# picoAvaR5.net
KiCad netlist of a schematic drawn in EAGLE
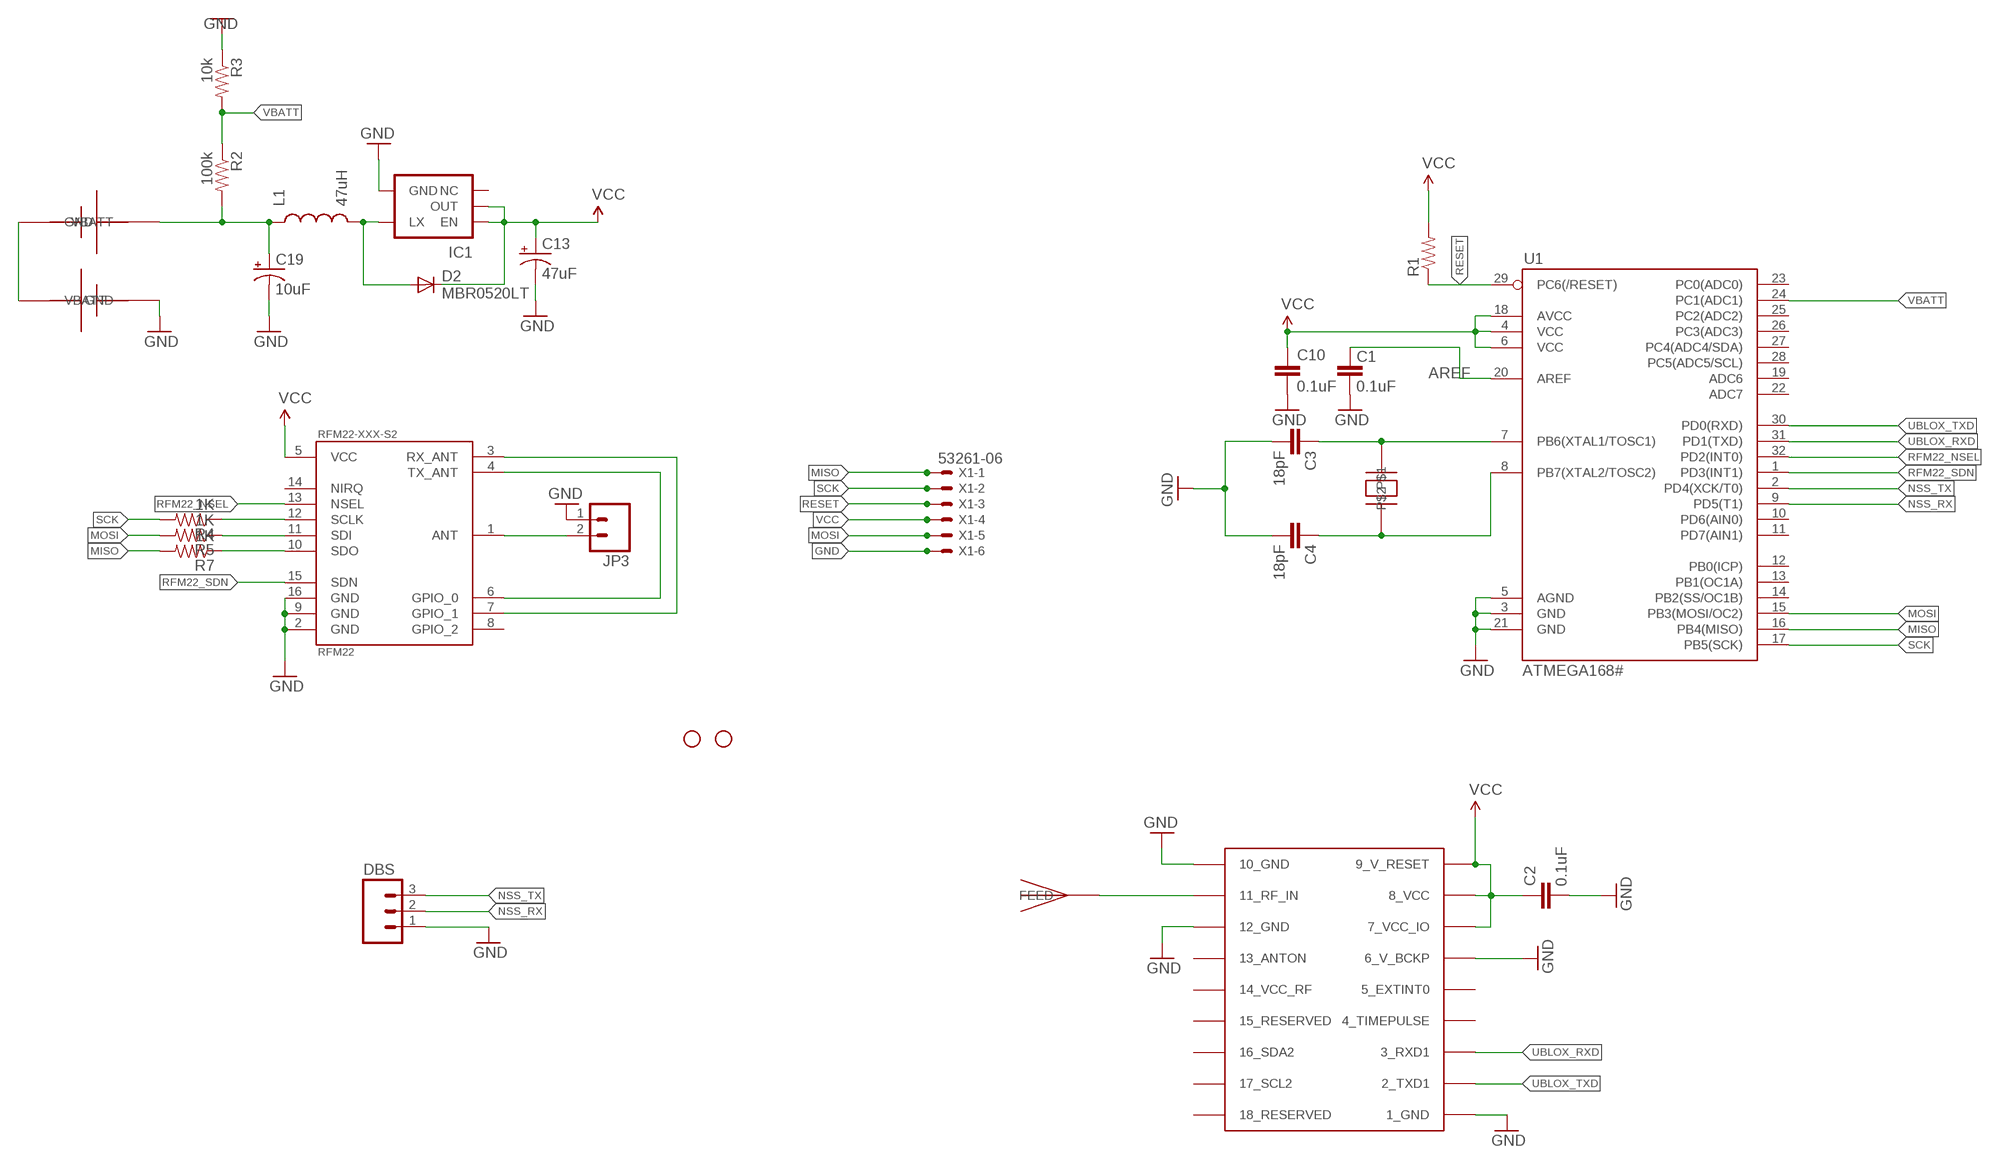
[diagram p0: schematic, sheet 1]

(export (version "E")
  (design (tool "Eeschema 10.0.6"))
  (components
    (comp (ref "C1")
      (value "0.1uF")
      (footprint "eagle-import:0402-CAP")
      (libsource (lib "eagle-import") (part "CAP0402-CAP"))
    )
    (comp (ref "C2")
      (value "0.1uF")
      (footprint "eagle-import:0402-CAP")
      (libsource (lib "eagle-import") (part "CAP0402-CAP"))
    )
    (comp (ref "C3")
      (value "18pF")
      (footprint "eagle-import:0402-CAP")
      (libsource (lib "eagle-import") (part "CAP0402-CAP"))
    )
    (comp (ref "C4")
      (value "18pF")
      (footprint "eagle-import:0402-CAP")
      (libsource (lib "eagle-import") (part "CAP0402-CAP"))
    )
    (comp (ref "C10")
      (value "0.1uF")
      (footprint "eagle-import:0402-CAP")
      (libsource (lib "eagle-import") (part "CAP0402-CAP"))
    )
    (comp (ref "C13")
      (value "47uF")
      (footprint "eagle-import:EIA3216")
      (libsource (lib "eagle-import") (part "CAP_POL1206"))
    )
    (comp (ref "C19")
      (value "10uF")
      (footprint "eagle-import:EIA3216")
      (libsource (lib "eagle-import") (part "CAP_POL1206"))
    )
    (comp (ref "D2")
      (value "MBR0520LT")
      (footprint "eagle-import:SOD123")
      (libsource (lib "eagle-import") (part "MBR0520LT"))
    )
    (comp (ref "DBS")
      (value "M03PTH")
      (footprint "eagle-import:1X03")
      (libsource (lib "eagle-import") (part "M03PTH"))
    )
    (comp (ref "IC1")
      (value "V_REG_NCP1400SOT23-5")
      (footprint "eagle-import:SOT23-5")
      (libsource (lib "eagle-import") (part "V_REG_NCP1400SOT23-5"))
    )
    (comp (ref "JP1")
      (value "STAND-OFF")
      (footprint "eagle-import:STAND-OFF")
      (libsource (lib "eagle-import") (part "STAND-OFF"))
    )
    (comp (ref "JP2")
      (value "STAND-OFF")
      (footprint "eagle-import:STAND-OFF")
      (libsource (lib "eagle-import") (part "STAND-OFF"))
    )
    (comp (ref "JP3")
      (value "M02PTH")
      (footprint "eagle-import:1X02")
      (libsource (lib "eagle-import") (part "M02PTH"))
    )
    (comp (ref "L1")
      (value "47uH")
      (footprint "eagle-import:1210")
      (libsource (lib "eagle-import") (part "INDUCTOR1210"))
    )
    (comp (ref "R1")
      (value "RESISTOR0402-RES")
      (footprint "eagle-import:0402-RES")
      (libsource (lib "eagle-import") (part "RESISTOR0402-RES"))
    )
    (comp (ref "R2")
      (value "100k")
      (footprint "eagle-import:0402-RES")
      (libsource (lib "eagle-import") (part "RESISTOR0402-RES"))
    )
    (comp (ref "R3")
      (value "10k")
      (footprint "eagle-import:0402-RES")
      (libsource (lib "eagle-import") (part "RESISTOR0402-RES"))
    )
    (comp (ref "R4")
      (value "1K")
      (footprint "eagle-import:0402-RES")
      (libsource (lib "eagle-import") (part "RESISTOR0402-RES"))
    )
    (comp (ref "R5")
      (value "1K")
      (footprint "eagle-import:0402-RES")
      (libsource (lib "eagle-import") (part "RESISTOR0402-RES"))
    )
    (comp (ref "R7")
      (value "1K")
      (footprint "eagle-import:0402-RES")
      (libsource (lib "eagle-import") (part "RESISTOR0402-RES"))
    )
    (comp (ref "RFM22-XXX-S2")
      (value "RFM22")
      (footprint "eagle-import:RFM22-XXX-S2")
      (libsource (lib "eagle-import") (part "RFM22"))
    )
    (comp (ref "U$1")
      (value "UBLOX_MAX-6")
      (footprint "eagle-import:UBLOX_MAX-6")
      (libsource (lib "eagle-import") (part "UBLOX_MAX-6"))
    )
    (comp (ref "U$2")
      (value "ABRACON_ABM3_CRYSTAL")
      (footprint "eagle-import:ABRACON_ABM3_CRYSTAL")
      (libsource (lib "eagle-import") (part "ABRACON_ABM3_CRYSTAL"))
    )
    (comp (ref "U$3")
      (value "JTI_ANTENNA-1575AT43A40")
      (footprint "eagle-import:JTI_ANTENNA-1575AT43A40")
      (libsource (lib "eagle-import") (part "JTI_ANTENNA-1575AT43A40"))
    )
    (comp (ref "U$4")
      (value "KEYSTONE-82-AAA-BATTERY-HOLDER")
      (footprint "eagle-import:KEYSTONE-82-AAA-BATTERY")
      (libsource (lib "eagle-import") (part "KEYSTONE-82-AAA-BATTERY-HOLDER"))
    )
    (comp (ref "U$5")
      (value "KEYSTONE-82-AAA-BATTERY-HOLDER")
      (footprint "eagle-import:KEYSTONE-82-AAA-BATTERY")
      (libsource (lib "eagle-import") (part "KEYSTONE-82-AAA-BATTERY-HOLDER"))
    )
    (comp (ref "U1")
      (value "ATMEGA168#")
      (footprint "eagle-import:TQFP32-08")
      (libsource (lib "eagle-import") (part "ATMEGA168"))
    )
    (comp (ref "X1")
      (value "53261-06")
      (footprint "eagle-import:53261-06")
      (libsource (lib "eagle-import") (part "53?-06261"))
    )
  )
  (nets
    (net (code "1") (name "/AREF") (class "Default")
      (node (ref "C1") (pin "2") (pinfunction "2_2") (pintype "passive"))
      (node (ref "U1") (pin "20") (pinfunction "AREF_20") (pintype "bidirectional"))
    )
    (net (code "2") (name "GND") (class "Default")
      (node (ref "C1") (pin "1") (pinfunction "1_1") (pintype "passive"))
      (node (ref "C10") (pin "2") (pinfunction "2_2") (pintype "passive"))
      (node (ref "C13") (pin "C") (pinfunction "-_C") (pintype "passive"))
      (node (ref "C19") (pin "C") (pinfunction "-_C") (pintype "passive"))
      (node (ref "C2") (pin "2") (pinfunction "2_2") (pintype "passive"))
      (node (ref "C3") (pin "2") (pinfunction "2_2") (pintype "passive"))
      (node (ref "C4") (pin "2") (pinfunction "2_2") (pintype "passive"))
      (node (ref "DBS") (pin "1") (pinfunction "1_1") (pintype "passive"))
      (node (ref "IC1") (pin "4") (pinfunction "GND_4") (pintype "input"))
      (node (ref "JP3") (pin "1") (pinfunction "1_1") (pintype "passive"))
      (node (ref "R3") (pin "1") (pinfunction "1_1") (pintype "passive"))
      (node (ref "RFM22-XXX-S2") (pin "16") (pinfunction "GND_16") (pintype "power_in"))
      (node (ref "RFM22-XXX-S2") (pin "2") (pinfunction "GND_2") (pintype "power_in"))
      (node (ref "RFM22-XXX-S2") (pin "9") (pinfunction "GND_9") (pintype "power_in"))
      (node (ref "U$1") (pin "10_GND") (pinfunction "10_GND_10_GND") (pintype "bidirectional"))
      (node (ref "U$1") (pin "12_GND") (pinfunction "12_GND_12_GND") (pintype "bidirectional"))
      (node (ref "U$1") (pin "1_GND") (pinfunction "1_GND_1_GND") (pintype "bidirectional"))
      (node (ref "U$1") (pin "6_V_BCKP") (pinfunction "6_V_BCKP_6_V_BCKP") (pintype "bidirectional"))
      (node (ref "U$5") (pin "GND") (pinfunction "GND_GND") (pintype "bidirectional"))
      (node (ref "U$5") (pin "GND2") (pinfunction "GND_GND2") (pintype "bidirectional"))
      (node (ref "U1") (pin "21") (pinfunction "GND_21") (pintype "bidirectional"))
      (node (ref "U1") (pin "3") (pinfunction "GND_3") (pintype "bidirectional"))
      (node (ref "U1") (pin "5") (pinfunction "AGND_5") (pintype "bidirectional"))
      (node (ref "X1") (pin "6") (pinfunction "S_6") (pintype "passive"))
    )
    (net (code "3") (name "MISO") (class "Default")
      (node (ref "R7") (pin "2") (pinfunction "2_2") (pintype "passive"))
      (node (ref "U1") (pin "16") (pinfunction "PB4(MISO)_16") (pintype "bidirectional"))
      (node (ref "X1") (pin "1") (pinfunction "S_1") (pintype "passive"))
    )
    (net (code "4") (name "MOSI") (class "Default")
      (node (ref "R5") (pin "2") (pinfunction "2_2") (pintype "passive"))
      (node (ref "U1") (pin "15") (pinfunction "PB3(MOSI/OC2)_15") (pintype "bidirectional"))
      (node (ref "X1") (pin "5") (pinfunction "S_5") (pintype "passive"))
    )
    (net (code "5") (name "NSS_RX") (class "Default")
      (node (ref "DBS") (pin "2") (pinfunction "2_2") (pintype "passive"))
      (node (ref "U1") (pin "9") (pinfunction "PD5(T1)_9") (pintype "bidirectional"))
    )
    (net (code "6") (name "NSS_TX") (class "Default")
      (node (ref "DBS") (pin "3") (pinfunction "3_3") (pintype "passive"))
      (node (ref "U1") (pin "2") (pinfunction "PD4(XCK/T0)_2") (pintype "bidirectional"))
    )
    (net (code "7") (name "Net-(C19-+)") (class "Default")
      (node (ref "C19") (pin "A") (pinfunction "+_A") (pintype "passive"))
      (node (ref "L1") (pin "1") (pinfunction "1_1") (pintype "passive"))
      (node (ref "R2") (pin "2") (pinfunction "2_2") (pintype "passive"))
      (node (ref "U$4") (pin "VBATT") (pinfunction "VBATT_VBATT") (pintype "bidirectional"))
      (node (ref "U$4") (pin "VBATT1") (pinfunction "VBATT_VBATT1") (pintype "bidirectional"))
    )
    (net (code "8") (name "Net-(IC1-LX)") (class "Default")
      (node (ref "D2") (pin "A") (pinfunction "A_A") (pintype "passive"))
      (node (ref "IC1") (pin "5") (pinfunction "LX_5") (pintype "input"))
      (node (ref "L1") (pin "2") (pinfunction "2_2") (pintype "passive"))
    )
    (net (code "9") (name "Net-(RFM22-XXX-S2-ANT)") (class "Default")
      (node (ref "JP3") (pin "2") (pinfunction "2_2") (pintype "passive"))
      (node (ref "RFM22-XXX-S2") (pin "1") (pinfunction "ANT_1") (pintype "bidirectional"))
    )
    (net (code "10") (name "Net-(RFM22-XXX-S2-GPIO_0)") (class "Default")
      (node (ref "RFM22-XXX-S2") (pin "4") (pinfunction "TX_ANT_4") (pintype "input"))
      (node (ref "RFM22-XXX-S2") (pin "6") (pinfunction "GPIO_0_6") (pintype "bidirectional"))
    )
    (net (code "11") (name "Net-(RFM22-XXX-S2-GPIO_1)") (class "Default")
      (node (ref "RFM22-XXX-S2") (pin "3") (pinfunction "RX_ANT_3") (pintype "input"))
      (node (ref "RFM22-XXX-S2") (pin "7") (pinfunction "GPIO_1_7") (pintype "bidirectional"))
    )
    (net (code "12") (name "Net-(RFM22-XXX-S2-SCLK)") (class "Default")
      (node (ref "R4") (pin "1") (pinfunction "1_1") (pintype "passive"))
      (node (ref "RFM22-XXX-S2") (pin "12") (pinfunction "SCLK_12") (pintype "input"))
    )
    (net (code "13") (name "Net-(RFM22-XXX-S2-SDI)") (class "Default")
      (node (ref "R5") (pin "1") (pinfunction "1_1") (pintype "passive"))
      (node (ref "RFM22-XXX-S2") (pin "11") (pinfunction "SDI_11") (pintype "input"))
    )
    (net (code "14") (name "Net-(RFM22-XXX-S2-SDO)") (class "Default")
      (node (ref "R7") (pin "1") (pinfunction "1_1") (pintype "passive"))
      (node (ref "RFM22-XXX-S2") (pin "10") (pinfunction "SDO_10") (pintype "output"))
    )
    (net (code "15") (name "Net-(U$1-Pad11_RF_IN)") (class "Default")
      (node (ref "U$1") (pin "11_RF_IN") (pinfunction "11_RF_IN_11_RF_IN") (pintype "bidirectional"))
      (node (ref "U$3") (pin "FEED") (pinfunction "FEED_FEED") (pintype "bidirectional"))
    )
    (net (code "16") (name "Net-(U$4-GND-PadGND2)") (class "Default")
      (node (ref "U$4") (pin "GND") (pinfunction "GND_GND") (pintype "bidirectional"))
      (node (ref "U$4") (pin "GND2") (pinfunction "GND_GND2") (pintype "bidirectional"))
      (node (ref "U$5") (pin "VBATT") (pinfunction "VBATT_VBATT") (pintype "bidirectional"))
      (node (ref "U$5") (pin "VBATT1") (pinfunction "VBATT_VBATT1") (pintype "bidirectional"))
    )
    (net (code "17") (name "Net-(U1-PB6(XTAL1{slash}TOSC1))") (class "Default")
      (node (ref "C3") (pin "1") (pinfunction "1_1") (pintype "passive"))
      (node (ref "U$2") (pin "P$2") (pinfunction "P$2_P$2") (pintype "bidirectional"))
      (node (ref "U1") (pin "7") (pinfunction "PB6(XTAL1/TOSC1)_7") (pintype "bidirectional"))
    )
    (net (code "18") (name "Net-(U1-PB7(XTAL2{slash}TOSC2))") (class "Default")
      (node (ref "C4") (pin "1") (pinfunction "1_1") (pintype "passive"))
      (node (ref "U$2") (pin "P$1") (pinfunction "P$1_P$1") (pintype "bidirectional"))
      (node (ref "U1") (pin "8") (pinfunction "PB7(XTAL2/TOSC2)_8") (pintype "bidirectional"))
    )
    (net (code "19") (name "RESET") (class "Default")
      (node (ref "R1") (pin "1") (pinfunction "1_1") (pintype "passive"))
      (node (ref "U1") (pin "29") (pinfunction "PC6(/RESET)_29") (pintype "bidirectional"))
      (node (ref "X1") (pin "3") (pinfunction "S_3") (pintype "passive"))
    )
    (net (code "20") (name "RFM22_NSEL") (class "Default")
      (node (ref "RFM22-XXX-S2") (pin "13") (pinfunction "NSEL_13") (pintype "input"))
      (node (ref "U1") (pin "32") (pinfunction "PD2(INT0)_32") (pintype "bidirectional"))
    )
    (net (code "21") (name "RFM22_SDN") (class "Default")
      (node (ref "RFM22-XXX-S2") (pin "15") (pinfunction "SDN_15") (pintype "input"))
      (node (ref "U1") (pin "1") (pinfunction "PD3(INT1)_1") (pintype "bidirectional"))
    )
    (net (code "22") (name "SCK") (class "Default")
      (node (ref "R4") (pin "2") (pinfunction "2_2") (pintype "passive"))
      (node (ref "U1") (pin "17") (pinfunction "PB5(SCK)_17") (pintype "bidirectional"))
      (node (ref "X1") (pin "2") (pinfunction "S_2") (pintype "passive"))
    )
    (net (code "23") (name "UBLOX_RXD") (class "Default")
      (node (ref "U$1") (pin "3_RXD1") (pinfunction "3_RXD1_3_RXD1") (pintype "bidirectional"))
      (node (ref "U1") (pin "31") (pinfunction "PD1(TXD)_31") (pintype "bidirectional"))
    )
    (net (code "24") (name "UBLOX_TXD") (class "Default")
      (node (ref "U$1") (pin "2_TXD1") (pinfunction "2_TXD1_2_TXD1") (pintype "bidirectional"))
      (node (ref "U1") (pin "30") (pinfunction "PD0(RXD)_30") (pintype "bidirectional"))
    )
    (net (code "25") (name "VBATT") (class "Default")
      (node (ref "R2") (pin "1") (pinfunction "1_1") (pintype "passive"))
      (node (ref "R3") (pin "2") (pinfunction "2_2") (pintype "passive"))
      (node (ref "U1") (pin "24") (pinfunction "PC1(ADC1)_24") (pintype "bidirectional"))
    )
    (net (code "26") (name "VCC") (class "Default")
      (node (ref "C10") (pin "1") (pinfunction "1_1") (pintype "passive"))
      (node (ref "C13") (pin "A") (pinfunction "+_A") (pintype "passive"))
      (node (ref "C2") (pin "1") (pinfunction "1_1") (pintype "passive"))
      (node (ref "D2") (pin "C") (pinfunction "C_C") (pintype "passive"))
      (node (ref "IC1") (pin "1") (pinfunction "EN_1") (pintype "input"))
      (node (ref "IC1") (pin "2") (pinfunction "OUT_2") (pintype "passive"))
      (node (ref "R1") (pin "2") (pinfunction "2_2") (pintype "passive"))
      (node (ref "RFM22-XXX-S2") (pin "5") (pinfunction "VCC_5") (pintype "bidirectional"))
      (node (ref "U$1") (pin "7_VCC_IO") (pinfunction "7_VCC_IO_7_VCC_IO") (pintype "bidirectional"))
      (node (ref "U$1") (pin "8_VCC") (pinfunction "8_VCC_8_VCC") (pintype "bidirectional"))
      (node (ref "U$1") (pin "9_V_RESET") (pinfunction "9_V_RESET_9_V_RESET") (pintype "bidirectional"))
      (node (ref "U1") (pin "18") (pinfunction "AVCC_18") (pintype "bidirectional"))
      (node (ref "U1") (pin "4") (pinfunction "VCC_4") (pintype "bidirectional"))
      (node (ref "U1") (pin "6") (pinfunction "VCC_6") (pintype "bidirectional"))
      (node (ref "X1") (pin "4") (pinfunction "S_4") (pintype "passive"))
    )
    (net (code "27") (name "unconnected-(IC1-NC-Pad3)") (class "Default")
      (node (ref "IC1") (pin "3") (pinfunction "NC_3") (pintype "input"))
    )
    (net (code "28") (name "unconnected-(RFM22-XXX-S2-GPIO_2-Pad8)") (class "Default")
      (node (ref "RFM22-XXX-S2") (pin "8") (pinfunction "GPIO_2_8") (pintype "bidirectional"))
    )
    (net (code "29") (name "unconnected-(RFM22-XXX-S2-NIRQ-Pad14)") (class "Default")
      (node (ref "RFM22-XXX-S2") (pin "14") (pinfunction "NIRQ_14") (pintype "output"))
    )
    (net (code "30") (name "unconnected-(U$1-Pad4_TIMEPULSE)") (class "Default")
      (node (ref "U$1") (pin "4_TIMEPULSE") (pinfunction "4_TIMEPULSE_4_TIMEPULSE") (pintype "bidirectional"))
    )
    (net (code "31") (name "unconnected-(U$1-Pad5_EXTINT0)") (class "Default")
      (node (ref "U$1") (pin "5_EXTINT0") (pinfunction "5_EXTINT0_5_EXTINT0") (pintype "bidirectional"))
    )
    (net (code "32") (name "unconnected-(U$1-Pad13_ANTON)") (class "Default")
      (node (ref "U$1") (pin "13_ANTON") (pinfunction "13_ANTON_13_ANTON") (pintype "bidirectional"))
    )
    (net (code "33") (name "unconnected-(U$1-Pad14_VCC_RF)") (class "Default")
      (node (ref "U$1") (pin "14_VCC_RF") (pinfunction "14_VCC_RF_14_VCC_RF") (pintype "bidirectional"))
    )
    (net (code "34") (name "unconnected-(U$1-Pad15_RESERVED)") (class "Default")
      (node (ref "U$1") (pin "15_RESERVED") (pinfunction "15_RESERVED_15_RESERVED") (pintype "bidirectional"))
    )
    (net (code "35") (name "unconnected-(U$1-Pad16_SDA2)") (class "Default")
      (node (ref "U$1") (pin "16_SDA2") (pinfunction "16_SDA2_16_SDA2") (pintype "bidirectional"))
    )
    (net (code "36") (name "unconnected-(U$1-Pad17_SCL2)") (class "Default")
      (node (ref "U$1") (pin "17_SCL2") (pinfunction "17_SCL2_17_SCL2") (pintype "bidirectional"))
    )
    (net (code "37") (name "unconnected-(U$1-Pad18_RESERVED)") (class "Default")
      (node (ref "U$1") (pin "18_RESERVED") (pinfunction "18_RESERVED_18_RESERVED") (pintype "bidirectional"))
    )
    (net (code "38") (name "unconnected-(U1-ADC6-Pad19)") (class "Default")
      (node (ref "U1") (pin "19") (pinfunction "ADC6_19") (pintype "bidirectional"))
    )
    (net (code "39") (name "unconnected-(U1-ADC7-Pad22)") (class "Default")
      (node (ref "U1") (pin "22") (pinfunction "ADC7_22") (pintype "bidirectional"))
    )
    (net (code "40") (name "unconnected-(U1-PB0(ICP)-Pad12)") (class "Default")
      (node (ref "U1") (pin "12") (pinfunction "PB0(ICP)_12") (pintype "bidirectional"))
    )
    (net (code "41") (name "unconnected-(U1-PB1(OC1A)-Pad13)") (class "Default")
      (node (ref "U1") (pin "13") (pinfunction "PB1(OC1A)_13") (pintype "bidirectional"))
    )
    (net (code "42") (name "unconnected-(U1-PB2(SS{slash}OC1B)-Pad14)") (class "Default")
      (node (ref "U1") (pin "14") (pinfunction "PB2(SS/OC1B)_14") (pintype "bidirectional"))
    )
    (net (code "43") (name "unconnected-(U1-PC0(ADC0)-Pad23)") (class "Default")
      (node (ref "U1") (pin "23") (pinfunction "PC0(ADC0)_23") (pintype "bidirectional"))
    )
    (net (code "44") (name "unconnected-(U1-PC2(ADC2)-Pad25)") (class "Default")
      (node (ref "U1") (pin "25") (pinfunction "PC2(ADC2)_25") (pintype "bidirectional"))
    )
    (net (code "45") (name "unconnected-(U1-PC3(ADC3)-Pad26)") (class "Default")
      (node (ref "U1") (pin "26") (pinfunction "PC3(ADC3)_26") (pintype "bidirectional"))
    )
    (net (code "46") (name "unconnected-(U1-PC4(ADC4{slash}SDA)-Pad27)") (class "Default")
      (node (ref "U1") (pin "27") (pinfunction "PC4(ADC4/SDA)_27") (pintype "bidirectional"))
    )
    (net (code "47") (name "unconnected-(U1-PC5(ADC5{slash}SCL)-Pad28)") (class "Default")
      (node (ref "U1") (pin "28") (pinfunction "PC5(ADC5/SCL)_28") (pintype "bidirectional"))
    )
    (net (code "48") (name "unconnected-(U1-PD6(AIN0)-Pad10)") (class "Default")
      (node (ref "U1") (pin "10") (pinfunction "PD6(AIN0)_10") (pintype "bidirectional"))
    )
    (net (code "49") (name "unconnected-(U1-PD7(AIN1)-Pad11)") (class "Default")
      (node (ref "U1") (pin "11") (pinfunction "PD7(AIN1)_11") (pintype "bidirectional"))
    )
  )
)
